# C64_CHARSETSw_4k.net
KiCad netlist of a schematic drawn in EAGLE
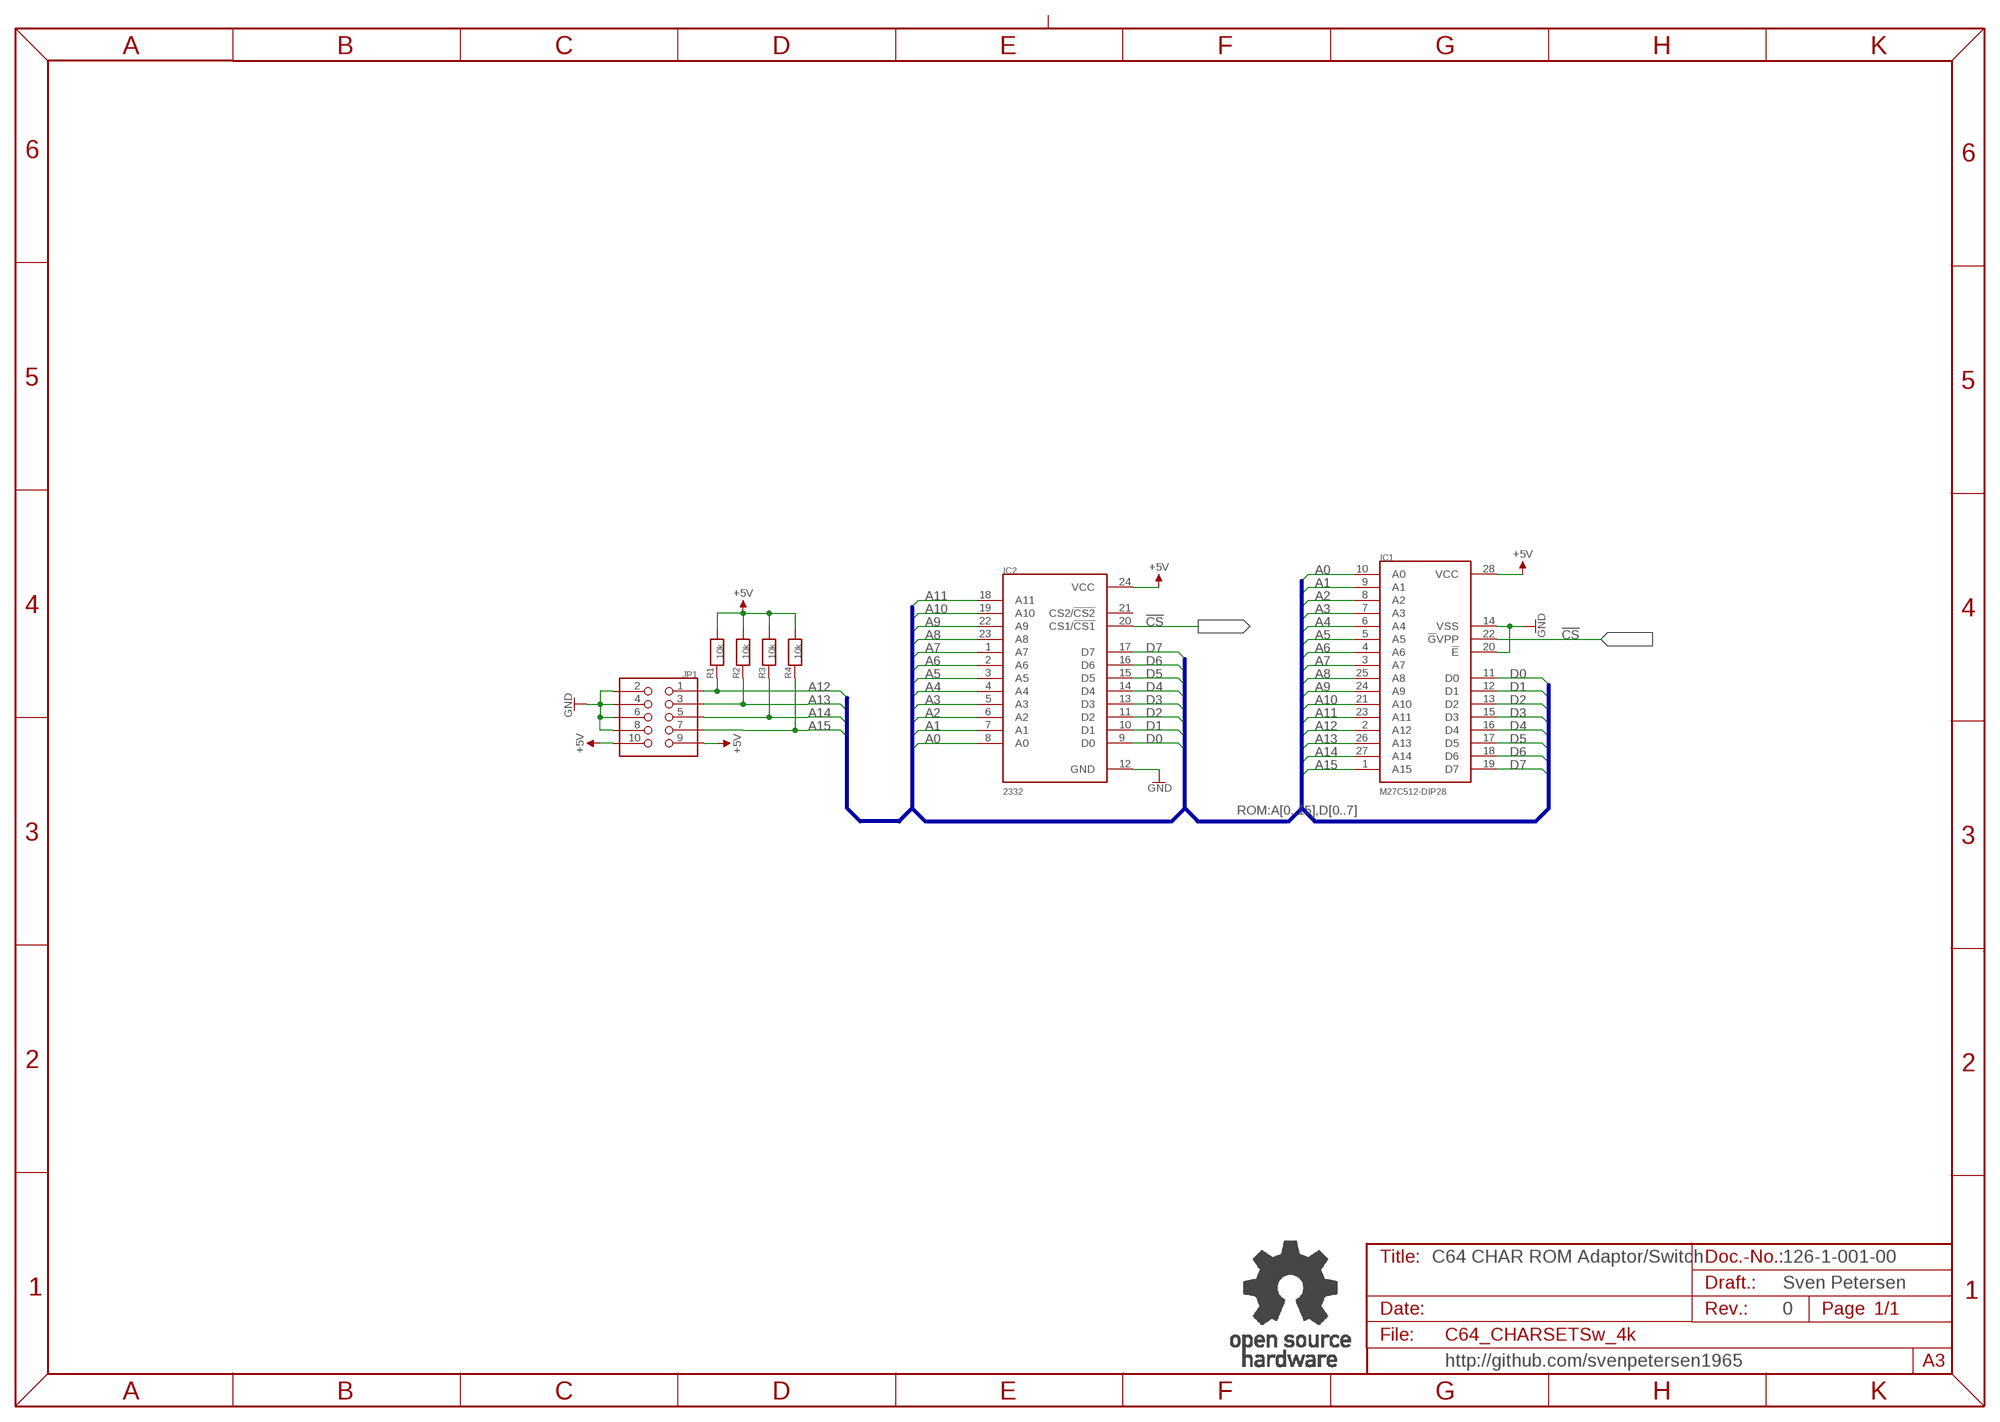
[diagram p0: schematic, sheet 1]

(export (version "E")
  (design (tool "Eeschema 10.0.6"))
  (components
    (comp (ref "IC1")
      (value "M27C512-DIP28")
      (footprint "eagle-import:DIL28-6")
      (libsource (lib "eagle-import") (part "M27C512-DIP28"))
    )
    (comp (ref "IC2")
      (value "2332")
      (footprint "eagle-import:DIL24_SOCKET")
      (libsource (lib "eagle-import") (part "2332"))
    )
    (comp (ref "JP1")
      (value "PINHD-2X590°/088")
      (footprint "eagle-import:2X05_90_SERIES_088")
      (libsource (lib "eagle-import") (part "PINHD-2X590°/088"))
    )
    (comp (ref "R1")
      (value "10k")
      (footprint "eagle-import:0805")
      (libsource (lib "eagle-import") (part "R-0805"))
    )
    (comp (ref "R2")
      (value "10k")
      (footprint "eagle-import:0805")
      (libsource (lib "eagle-import") (part "R-0805"))
    )
    (comp (ref "R3")
      (value "10k")
      (footprint "eagle-import:0805")
      (libsource (lib "eagle-import") (part "R-0805"))
    )
    (comp (ref "R4")
      (value "10k")
      (footprint "eagle-import:0805")
      (libsource (lib "eagle-import") (part "R-0805"))
    )
    (comp (ref "U$6")
      (value "OPEN_SOURCE_HW")
      (footprint "eagle-import:OPENHW")
      (libsource (lib "eagle-import") (part "OPEN_SOURCE_HW"))
    )
  )
  (nets
    (net (code "1") (name "+5V") (class "Default")
      (node (ref "IC1") (pin "28") (pinfunction "VCC_28") (pintype "power_in"))
      (node (ref "IC2") (pin "24") (pinfunction "VCC_24") (pintype "power_in"))
      (node (ref "JP1") (pin "10") (pinfunction "10_10") (pintype "passive"))
      (node (ref "JP1") (pin "9") (pinfunction "9_9") (pintype "passive"))
      (node (ref "R1") (pin "2") (pinfunction "2_2") (pintype "passive"))
      (node (ref "R2") (pin "2") (pinfunction "2_2") (pintype "passive"))
      (node (ref "R3") (pin "2") (pinfunction "2_2") (pintype "passive"))
      (node (ref "R4") (pin "2") (pinfunction "2_2") (pintype "passive"))
    )
    (net (code "2") (name "/A0") (class "Default")
      (node (ref "IC1") (pin "10") (pinfunction "A0_10") (pintype "input"))
      (node (ref "IC2") (pin "8") (pinfunction "A0_8") (pintype "input"))
    )
    (net (code "3") (name "/A1") (class "Default")
      (node (ref "IC1") (pin "9") (pinfunction "A1_9") (pintype "input"))
      (node (ref "IC2") (pin "7") (pinfunction "A1_7") (pintype "input"))
    )
    (net (code "4") (name "/A2") (class "Default")
      (node (ref "IC1") (pin "8") (pinfunction "A2_8") (pintype "input"))
      (node (ref "IC2") (pin "6") (pinfunction "A2_6") (pintype "input"))
    )
    (net (code "5") (name "/A3") (class "Default")
      (node (ref "IC1") (pin "7") (pinfunction "A3_7") (pintype "input"))
      (node (ref "IC2") (pin "5") (pinfunction "A3_5") (pintype "input"))
    )
    (net (code "6") (name "/A4") (class "Default")
      (node (ref "IC1") (pin "6") (pinfunction "A4_6") (pintype "input"))
      (node (ref "IC2") (pin "4") (pinfunction "A4_4") (pintype "input"))
    )
    (net (code "7") (name "/A5") (class "Default")
      (node (ref "IC1") (pin "5") (pinfunction "A5_5") (pintype "input"))
      (node (ref "IC2") (pin "3") (pinfunction "A5_3") (pintype "input"))
    )
    (net (code "8") (name "/A6") (class "Default")
      (node (ref "IC1") (pin "4") (pinfunction "A6_4") (pintype "input"))
      (node (ref "IC2") (pin "2") (pinfunction "A6_2") (pintype "input"))
    )
    (net (code "9") (name "/A7") (class "Default")
      (node (ref "IC1") (pin "3") (pinfunction "A7_3") (pintype "input"))
      (node (ref "IC2") (pin "1") (pinfunction "A7_1") (pintype "input"))
    )
    (net (code "10") (name "/A8") (class "Default")
      (node (ref "IC1") (pin "25") (pinfunction "A8_25") (pintype "input"))
      (node (ref "IC2") (pin "23") (pinfunction "A8_23") (pintype "input"))
    )
    (net (code "11") (name "/A9") (class "Default")
      (node (ref "IC1") (pin "24") (pinfunction "A9_24") (pintype "input"))
      (node (ref "IC2") (pin "22") (pinfunction "A9_22") (pintype "input"))
    )
    (net (code "12") (name "/A10") (class "Default")
      (node (ref "IC1") (pin "21") (pinfunction "A10_21") (pintype "input"))
      (node (ref "IC2") (pin "19") (pinfunction "A10_19") (pintype "input"))
    )
    (net (code "13") (name "/A11") (class "Default")
      (node (ref "IC1") (pin "23") (pinfunction "A11_23") (pintype "input"))
      (node (ref "IC2") (pin "18") (pinfunction "A11_18") (pintype "input"))
    )
    (net (code "14") (name "/A12") (class "Default")
      (node (ref "IC1") (pin "2") (pinfunction "A12_2") (pintype "input"))
      (node (ref "JP1") (pin "1") (pinfunction "1_1") (pintype "passive"))
      (node (ref "R1") (pin "1") (pinfunction "1_1") (pintype "passive"))
    )
    (net (code "15") (name "/A13") (class "Default")
      (node (ref "IC1") (pin "26") (pinfunction "A13_26") (pintype "input"))
      (node (ref "JP1") (pin "3") (pinfunction "3_3") (pintype "passive"))
      (node (ref "R2") (pin "1") (pinfunction "1_1") (pintype "passive"))
    )
    (net (code "16") (name "/A14") (class "Default")
      (node (ref "IC1") (pin "27") (pinfunction "A14_27") (pintype "input"))
      (node (ref "JP1") (pin "5") (pinfunction "5_5") (pintype "passive"))
      (node (ref "R3") (pin "1") (pinfunction "1_1") (pintype "passive"))
    )
    (net (code "17") (name "/A15") (class "Default")
      (node (ref "IC1") (pin "1") (pinfunction "A15_1") (pintype "input"))
      (node (ref "JP1") (pin "7") (pinfunction "7_7") (pintype "passive"))
      (node (ref "R4") (pin "1") (pinfunction "1_1") (pintype "passive"))
    )
    (net (code "18") (name "/D0") (class "Default")
      (node (ref "IC1") (pin "11") (pinfunction "D0_11") (pintype "bidirectional"))
      (node (ref "IC2") (pin "9") (pinfunction "D0_9") (pintype "tri_state"))
    )
    (net (code "19") (name "/D1") (class "Default")
      (node (ref "IC1") (pin "12") (pinfunction "D1_12") (pintype "bidirectional"))
      (node (ref "IC2") (pin "10") (pinfunction "D1_10") (pintype "tri_state"))
    )
    (net (code "20") (name "/D2") (class "Default")
      (node (ref "IC1") (pin "13") (pinfunction "D2_13") (pintype "bidirectional"))
      (node (ref "IC2") (pin "11") (pinfunction "D2_11") (pintype "tri_state"))
    )
    (net (code "21") (name "/D3") (class "Default")
      (node (ref "IC1") (pin "15") (pinfunction "D3_15") (pintype "bidirectional"))
      (node (ref "IC2") (pin "13") (pinfunction "D3_13") (pintype "tri_state"))
    )
    (net (code "22") (name "/D4") (class "Default")
      (node (ref "IC1") (pin "16") (pinfunction "D4_16") (pintype "bidirectional"))
      (node (ref "IC2") (pin "14") (pinfunction "D4_14") (pintype "tri_state"))
    )
    (net (code "23") (name "/D5") (class "Default")
      (node (ref "IC1") (pin "17") (pinfunction "D5_17") (pintype "bidirectional"))
      (node (ref "IC2") (pin "15") (pinfunction "D5_15") (pintype "tri_state"))
    )
    (net (code "24") (name "/D6") (class "Default")
      (node (ref "IC1") (pin "18") (pinfunction "D6_18") (pintype "bidirectional"))
      (node (ref "IC2") (pin "16") (pinfunction "D6_16") (pintype "tri_state"))
    )
    (net (code "25") (name "/D7") (class "Default")
      (node (ref "IC1") (pin "19") (pinfunction "D7_19") (pintype "bidirectional"))
      (node (ref "IC2") (pin "17") (pinfunction "D7_17") (pintype "tri_state"))
    )
    (net (code "27") (name "/~{CS}") (class "Default")
      (node (ref "IC1") (pin "22") (pinfunction "~{G}VPP_22") (pintype "input"))
      (node (ref "IC2") (pin "20") (pinfunction "CS1/~{CS1}_20") (pintype "input"))
    )
    (net (code "28") (name "GND") (class "Default")
      (node (ref "IC1") (pin "14") (pinfunction "VSS_14") (pintype "power_in"))
      (node (ref "IC1") (pin "20") (pinfunction "~{E}_20") (pintype "input"))
      (node (ref "IC2") (pin "12") (pinfunction "GND_12") (pintype "power_in"))
      (node (ref "JP1") (pin "2") (pinfunction "2_2") (pintype "passive"))
      (node (ref "JP1") (pin "4") (pinfunction "4_4") (pintype "passive"))
      (node (ref "JP1") (pin "6") (pinfunction "6_6") (pintype "passive"))
      (node (ref "JP1") (pin "8") (pinfunction "8_8") (pintype "passive"))
    )
    (net (code "29") (name "unconnected-(IC2-CS2{slash}~{CS2}-Pad21)") (class "Default")
      (node (ref "IC2") (pin "21") (pinfunction "CS2/~{CS2}_21") (pintype "input"))
    )
  )
)
